# AutoReverseAVR.net
KiCad netlist of a schematic drawn in Altium Designer
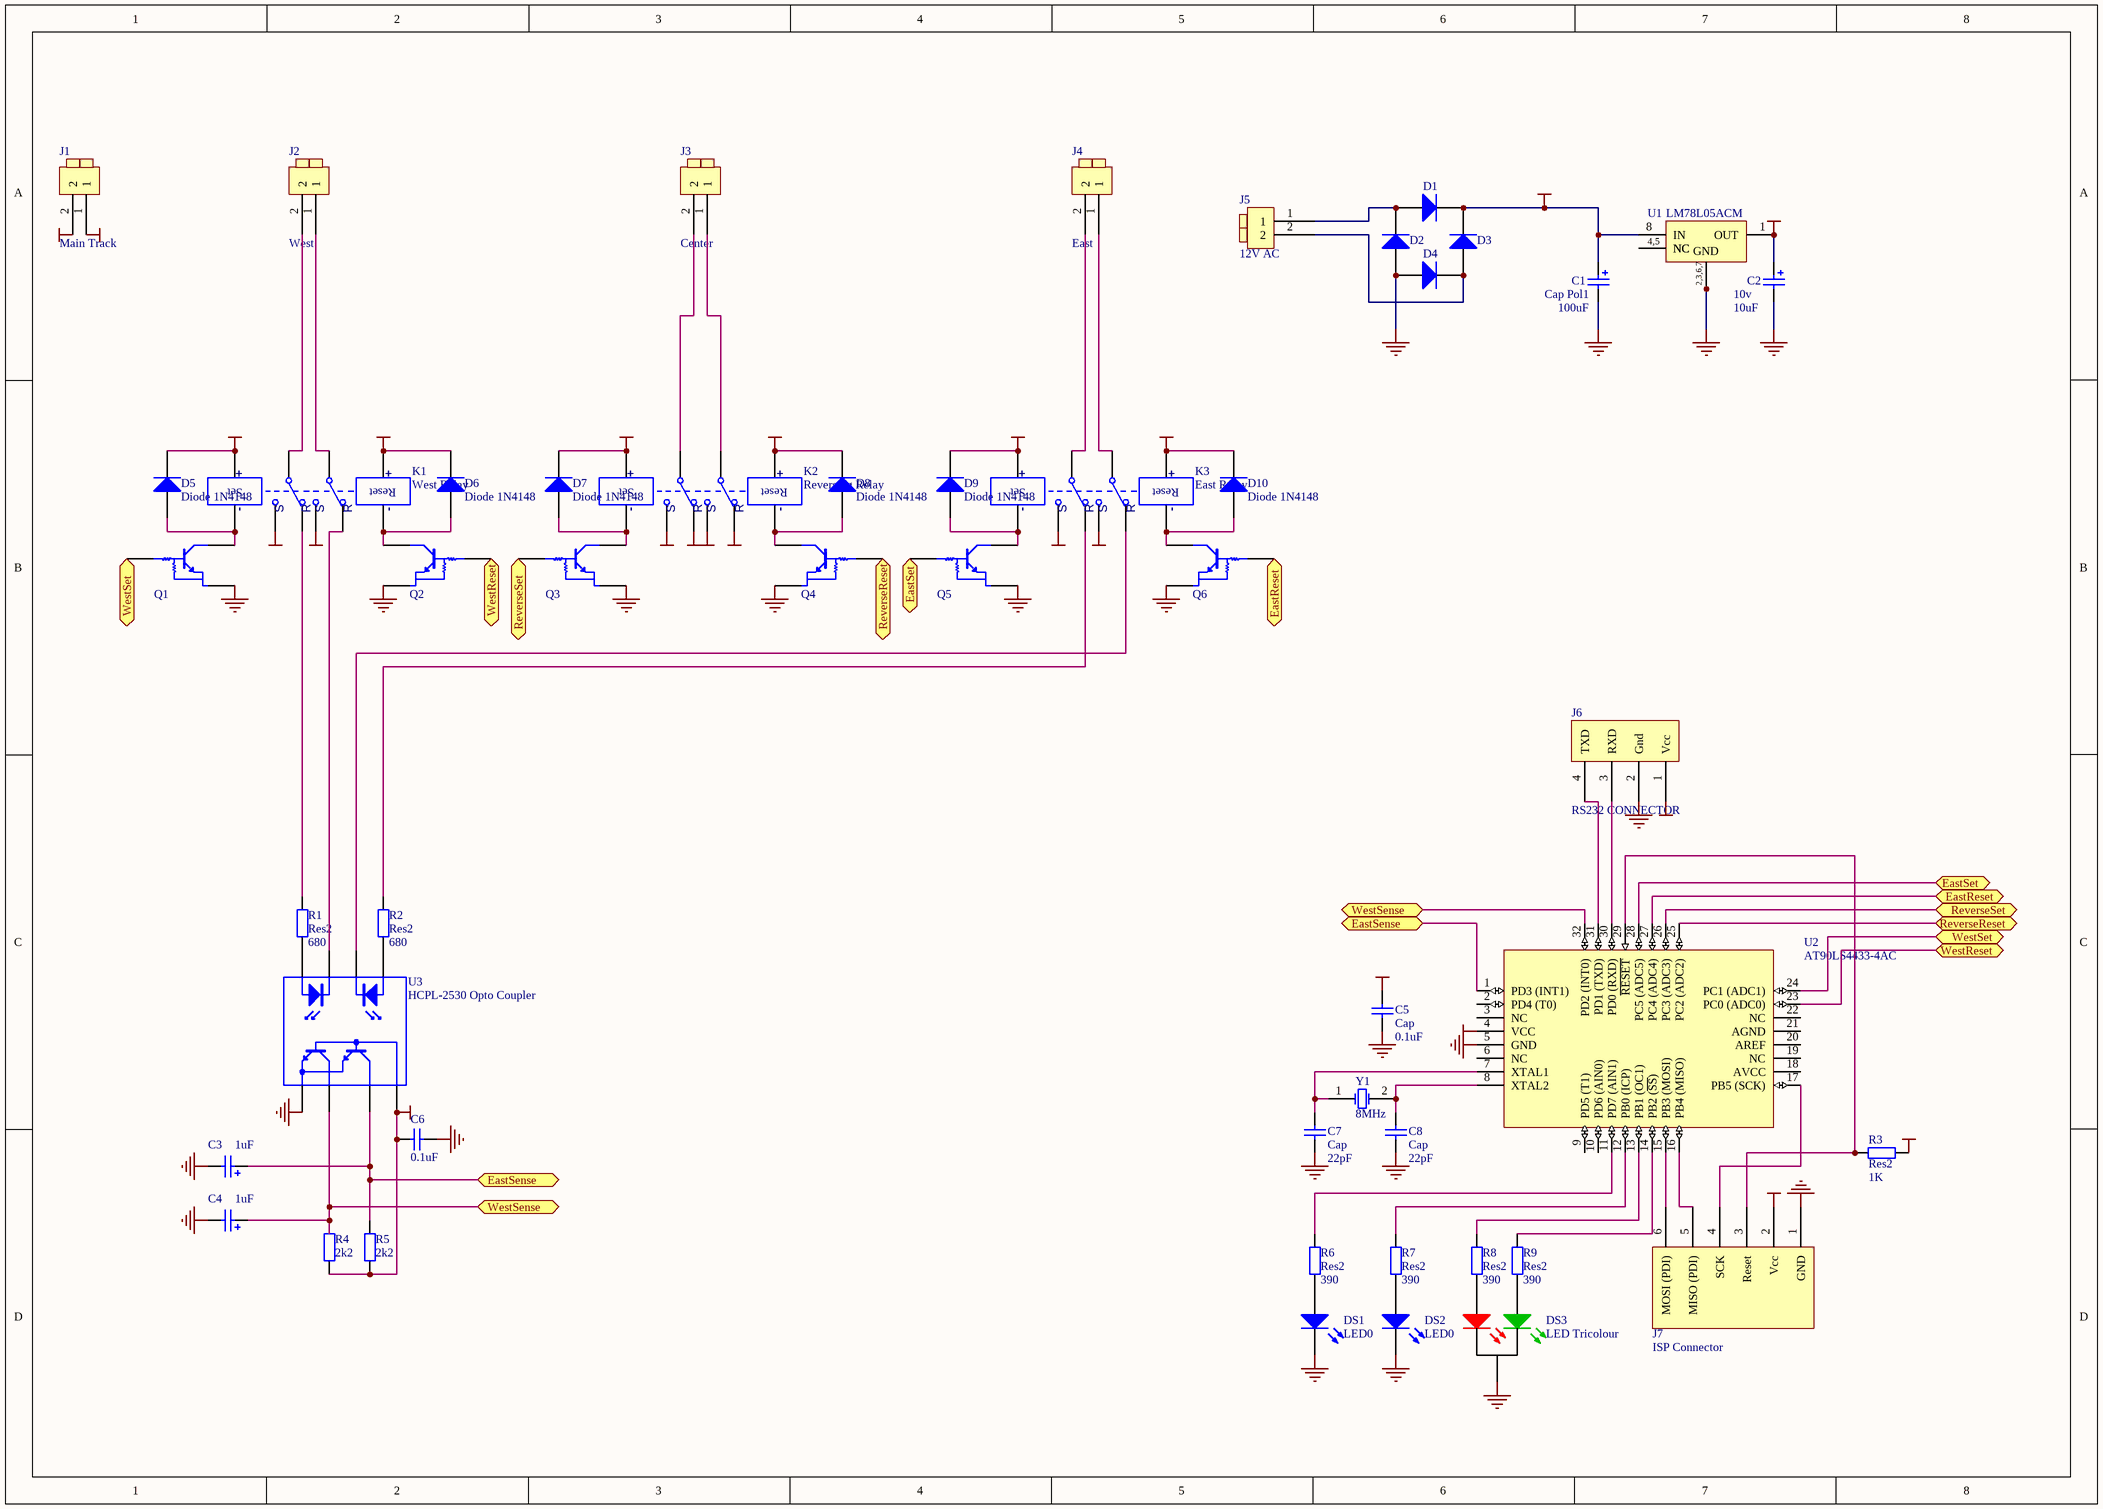
[diagram p0: AutoReverseAVR.SchDoc]

(export (version "E")
  (design (tool "Eeschema 10.0.6"))
  (components
    (comp (ref "C1")
      (value "Cap Pol1")
      (footprint "CAPPR5-10X10.5")
      (description "Polarized Capacitor (Radial)")
      (fields (field (name "ALTIUM_VALUE") "100uF") (field (name "PUBLISHER") "Altium Limited"))
      (libsource (lib "Miscellaneous Devices") (part "Cap Pol1"))
    )
    (comp (ref "C2")
      (value "10v")
      (footprint "CC3216-1206")
      (description "Polarized Capacitor (Radial)")
      (fields (field (name "ALTIUM_VALUE") "10uF") (field (name "PUBLISHER") "Altium Limited"))
      (libsource (lib "Miscellaneous Devices") (part "Cap Pol1"))
    )
    (comp (ref "C3")
      (value "1uF")
      (footprint "CC3216-1206")
      (description "Polarized Capacitor (Radial)")
      (fields (field (name "Comment") "Cap Pol1") (field (name "PUBLISHER") "Altium Limited"))
      (libsource (lib "Miscellaneous Devices") (part "Cap Pol1"))
    )
    (comp (ref "C4")
      (value "1uF")
      (footprint "CC3216-1206")
      (description "Polarized Capacitor (Radial)")
      (fields (field (name "Comment") "Cap Pol1") (field (name "PUBLISHER") "Altium Limited"))
      (libsource (lib "Miscellaneous Devices") (part "Cap Pol1"))
    )
    (comp (ref "C5")
      (value "Cap")
      (footprint "CC2012-0805")
      (description "Capacitor")
      (fields (field (name "ALTIUM_VALUE") "0.1uF") (field (name "PUBLISHER") "Altium Limited"))
      (libsource (lib "Miscellaneous Devices") (part "Cap"))
    )
    (comp (ref "C6")
      (value "0.1uF")
      (footprint "CC2012-0805")
      (description "Capacitor")
      (fields (field (name "Comment") "Cap") (field (name "PUBLISHER") "Altium Limited"))
      (libsource (lib "Miscellaneous Devices") (part "Cap"))
    )
    (comp (ref "C7")
      (value "Cap")
      (footprint "CC2012-0805")
      (description "Capacitor")
      (fields (field (name "ALTIUM_VALUE") "22pF") (field (name "PUBLISHER") "Altium Limited"))
      (libsource (lib "Miscellaneous Devices") (part "Cap"))
    )
    (comp (ref "C8")
      (value "Cap")
      (footprint "CC2012-0805")
      (description "Capacitor")
      (fields (field (name "ALTIUM_VALUE") "22pF") (field (name "PUBLISHER") "Altium Limited"))
      (libsource (lib "Miscellaneous Devices") (part "Cap"))
    )
    (comp (ref "D1")
      (value "Diode 1N4004")
      (footprint "DIO10.46-5.3x2.8")
      (description "1 Amp General Purpose Rectifier")
      (fields (field (name "PUBLISHER") "Altium Limited"))
      (libsource (lib "Miscellaneous Devices") (part "Diode 1N4004"))
    )
    (comp (ref "D2")
      (value "Diode 1N4004")
      (footprint "DIO10.46-5.3x2.8")
      (description "1 Amp General Purpose Rectifier")
      (fields (field (name "PUBLISHER") "Altium Limited"))
      (libsource (lib "Miscellaneous Devices") (part "Diode 1N4004"))
    )
    (comp (ref "D3")
      (value "Diode 1N4004")
      (footprint "DIO10.46-5.3x2.8")
      (description "1 Amp General Purpose Rectifier")
      (fields (field (name "PUBLISHER") "Altium Limited"))
      (libsource (lib "Miscellaneous Devices") (part "Diode 1N4004"))
    )
    (comp (ref "D4")
      (value "Diode 1N4004")
      (footprint "DIO10.46-5.3x2.8")
      (description "1 Amp General Purpose Rectifier")
      (fields (field (name "PUBLISHER") "Altium Limited"))
      (libsource (lib "Miscellaneous Devices") (part "Diode 1N4004"))
    )
    (comp (ref "D5")
      (value "Diode 1N4148")
      (footprint "DIO7.1-3.9x1.9")
      (description "High Conductance Fast Diode")
      (fields (field (name "PUBLISHER") "Altium Limited"))
      (libsource (lib "Miscellaneous Devices") (part "Diode 1N4148"))
    )
    (comp (ref "D6")
      (value "Diode 1N4148")
      (footprint "DIO7.1-3.9x1.9")
      (description "High Conductance Fast Diode")
      (fields (field (name "PUBLISHER") "Altium Limited"))
      (libsource (lib "Miscellaneous Devices") (part "Diode 1N4148"))
    )
    (comp (ref "D7")
      (value "Diode 1N4148")
      (footprint "DIO7.1-3.9x1.9")
      (description "High Conductance Fast Diode")
      (fields (field (name "PUBLISHER") "Altium Limited"))
      (libsource (lib "Miscellaneous Devices") (part "Diode 1N4148"))
    )
    (comp (ref "D8")
      (value "Diode 1N4148")
      (footprint "DIO7.1-3.9x1.9")
      (description "High Conductance Fast Diode")
      (fields (field (name "PUBLISHER") "Altium Limited"))
      (libsource (lib "Miscellaneous Devices") (part "Diode 1N4148"))
    )
    (comp (ref "D9")
      (value "Diode 1N4148")
      (footprint "DIO7.1-3.9x1.9")
      (description "High Conductance Fast Diode")
      (fields (field (name "PUBLISHER") "Altium Limited"))
      (libsource (lib "Miscellaneous Devices") (part "Diode 1N4148"))
    )
    (comp (ref "D10")
      (value "Diode 1N4148")
      (footprint "DIO7.1-3.9x1.9")
      (description "High Conductance Fast Diode")
      (fields (field (name "PUBLISHER") "Altium Limited"))
      (libsource (lib "Miscellaneous Devices") (part "Diode 1N4148"))
    )
    (comp (ref "DS1")
      (value "LED0")
      (footprint "LED3mm")
      (description "Typical INFRARED GaAs LED")
      (fields (field (name "PUBLISHER") "Altium Limited"))
      (libsource (lib "Miscellaneous Devices") (part "LED0"))
    )
    (comp (ref "DS2")
      (value "LED0")
      (footprint "LED3mm")
      (description "Typical INFRARED GaAs LED")
      (fields (field (name "PUBLISHER") "Altium Limited"))
      (libsource (lib "Miscellaneous Devices") (part "LED0"))
    )
    (comp (ref "DS3")
      (value "LED Tricolour")
      (footprint "LED3mm TriColour")
      (description "Typical Red Green Tri Color LED")
      (fields (field (name "PUBLISHER") "Altium Limited"))
      (libsource (lib "Custom") (part "LED Tricolour"))
    )
    (comp (ref "J1")
      (value "Main Track")
      (footprint "Screw Terminal 2 way 0.2")
      (libsource (lib "") (part "Screw Terminal 2 Way_1"))
    )
    (comp (ref "J2")
      (value "West")
      (footprint "Screw Terminal 2 way 0.2")
      (libsource (lib "") (part "Screw Terminal 2 Way_1"))
    )
    (comp (ref "J3")
      (value "Center")
      (footprint "Screw Terminal 2 way 0.2")
      (libsource (lib "") (part "Screw Terminal 2 Way_1"))
    )
    (comp (ref "J4")
      (value "East")
      (footprint "Screw Terminal 2 way 0.2")
      (libsource (lib "") (part "Screw Terminal 2 Way_1"))
    )
    (comp (ref "J5")
      (value "12V AC")
      (footprint "Screw Terminal 2 way 0.2")
      (libsource (lib "Custom") (part "Screw Terminal 2 Way"))
    )
    (comp (ref "J6")
      (value "RS232 CONNECTOR")
      (footprint "0.1 SIP 4 PIN")
      (libsource (lib "Custom") (part "RS232 CONNECTOR"))
    )
    (comp (ref "J7")
      (value "ISP Connector")
      (footprint "0.1 SIP 6 PIN")
      (libsource (lib "Custom") (part "ISP Connector"))
    )
    (comp (ref "K1")
      (value "West Relay")
      (footprint "DIP-10")
      (description "EA2-5T Dual Coil 5V Latching Relay")
      (fields (field (name "PUBLISHER") "Altium Limited"))
      (libsource (lib "Custom") (part "EA2-5T Dual Coil 5V Latching Relay"))
    )
    (comp (ref "K2")
      (value "Reversing Relay")
      (footprint "DIP-10")
      (description "EA2-5T Dual Coil 5V Latching Relay")
      (fields (field (name "PUBLISHER") "Altium Limited"))
      (libsource (lib "Custom") (part "EA2-5T Dual Coil 5V Latching Relay"))
    )
    (comp (ref "K3")
      (value "East Relay")
      (footprint "DIP-10")
      (description "EA2-5T Dual Coil 5V Latching Relay")
      (fields (field (name "PUBLISHER") "Altium Limited"))
      (libsource (lib "Custom") (part "EA2-5T Dual Coil 5V Latching Relay"))
    )
    (comp (ref "Q1")
      (value "~")
      (footprint "SO-G3")
      (description "Bias Resistor Transistor")
      (libsource (lib "Custom") (part "UN2212"))
    )
    (comp (ref "Q2")
      (value "~")
      (footprint "SO-G3")
      (description "Bias Resistor Transistor")
      (libsource (lib "Custom") (part "UN2212"))
    )
    (comp (ref "Q3")
      (value "~")
      (footprint "SO-G3")
      (description "Bias Resistor Transistor")
      (libsource (lib "Custom") (part "UN2212"))
    )
    (comp (ref "Q4")
      (value "~")
      (footprint "SO-G3")
      (description "Bias Resistor Transistor")
      (libsource (lib "Custom") (part "UN2212"))
    )
    (comp (ref "Q5")
      (value "~")
      (footprint "SO-G3")
      (description "Bias Resistor Transistor")
      (libsource (lib "Custom") (part "UN2212"))
    )
    (comp (ref "Q6")
      (value "~")
      (footprint "SO-G3")
      (description "Bias Resistor Transistor")
      (libsource (lib "Custom") (part "UN2212"))
    )
    (comp (ref "R1")
      (value "Res2")
      (footprint "CR2012-0805")
      (description "Resistor")
      (fields (field (name "ALTIUM_VALUE") "680") (field (name "PUBLISHER") "Altium Limited"))
      (libsource (lib "Miscellaneous Devices") (part "Res2"))
    )
    (comp (ref "R2")
      (value "Res2")
      (footprint "CR2012-0805")
      (description "Resistor")
      (fields (field (name "ALTIUM_VALUE") "680") (field (name "PUBLISHER") "Altium Limited"))
      (libsource (lib "Miscellaneous Devices") (part "Res2"))
    )
    (comp (ref "R3")
      (value "Res2")
      (footprint "CR2012-0805")
      (description "Resistor")
      (fields (field (name "ALTIUM_VALUE") "1K") (field (name "PUBLISHER") "Altium Limited"))
      (libsource (lib "") (part "Res2_1"))
    )
    (comp (ref "R4")
      (value "2k2")
      (footprint "CR2012-0805")
      (description "Resistor")
      (fields (field (name "Comment") "Res2") (field (name "PUBLISHER") "Altium Limited"))
      (libsource (lib "") (part "Res2_2"))
    )
    (comp (ref "R5")
      (value "2k2")
      (footprint "CR2012-0805")
      (description "Resistor")
      (fields (field (name "Comment") "Res2") (field (name "PUBLISHER") "Altium Limited"))
      (libsource (lib "") (part "Res2_2"))
    )
    (comp (ref "R6")
      (value "Res2")
      (footprint "CR2012-0805")
      (description "Resistor")
      (fields (field (name "ALTIUM_VALUE") "390") (field (name "PUBLISHER") "Altium Limited"))
      (libsource (lib "Miscellaneous Devices") (part "Res2"))
    )
    (comp (ref "R7")
      (value "Res2")
      (footprint "CR2012-0805")
      (description "Resistor")
      (fields (field (name "ALTIUM_VALUE") "390") (field (name "PUBLISHER") "Altium Limited"))
      (libsource (lib "Miscellaneous Devices") (part "Res2"))
    )
    (comp (ref "R8")
      (value "Res2")
      (footprint "CR2012-0805")
      (description "Resistor")
      (fields (field (name "ALTIUM_VALUE") "390") (field (name "PUBLISHER") "Altium Limited"))
      (libsource (lib "Miscellaneous Devices") (part "Res2"))
    )
    (comp (ref "R9")
      (value "Res2")
      (footprint "CR2012-0805")
      (description "Resistor")
      (fields (field (name "ALTIUM_VALUE") "390") (field (name "PUBLISHER") "Altium Limited"))
      (libsource (lib "Miscellaneous Devices") (part "Res2"))
    )
    (comp (ref "U1")
      (value "LM78L05ACM")
      (footprint "M08A")
      (description "3-Terminal Positive Regulator")
      (fields (field (name "PUBLISHER") "Altium Limited"))
      (libsource (lib "NSC Power Mgt Voltage Regulator") (part "LM78L05ACM"))
    )
    (comp (ref "U2")
      (value "AT90LS4433-4AC")
      (footprint "32A")
      (description "8-Bit AVR Microcontroller with 4K Bytes of In-System Programmable Flash Memory")
      (fields (field (name "PUBLISHER") "Altium Limited"))
      (libsource (lib "Custom") (part "AT90LS4433-4AC"))
    )
    (comp (ref "U3")
      (value "HCPL-2530 Opto Coupler")
      (footprint "8P3")
      (libsource (lib "Custom") (part "HCPL-2530"))
    )
    (comp (ref "Y1")
      (value "8MHz")
      (footprint "RAD-0.2")
      (description "Crystal Oscillator")
      (fields (field (name "PUBLISHER") "Altium Limited"))
      (libsource (lib "Miscellaneous Devices") (part "XTAL"))
    )
  )
  (nets
    (net (code "1") (name "/EastReset") (class "Default")
      (node (ref "Q6") (pin "1") (pinfunction "B_1") (pintype "passive"))
      (node (ref "U2") (pin "27") (pinfunction "PC4_(ADC4)_27") (pintype "bidirectional"))
    )
    (net (code "2") (name "/EastSense") (class "Default")
      (node (ref "C3") (pin "1") (pinfunction "1_1") (pintype "passive"))
      (node (ref "R5") (pin "1") (pinfunction "1_1") (pintype "passive"))
      (node (ref "U2") (pin "1") (pinfunction "PD3_(INT1)_1") (pintype "bidirectional"))
      (node (ref "U3") (pin "7") (pinfunction "C_7") (pintype "passive"))
    )
    (net (code "3") (name "/EastSet") (class "Default")
      (node (ref "Q5") (pin "1") (pinfunction "B_1") (pintype "passive"))
      (node (ref "U2") (pin "28") (pinfunction "PC5_(ADC5)_28") (pintype "bidirectional"))
    )
    (net (code "4") (name "/ReverseReset") (class "Default")
      (node (ref "Q4") (pin "1") (pinfunction "B_1") (pintype "passive"))
      (node (ref "U2") (pin "25") (pinfunction "PC2_(ADC2)_25") (pintype "bidirectional"))
    )
    (net (code "5") (name "/ReverseSet") (class "Default")
      (node (ref "Q3") (pin "1") (pinfunction "B_1") (pintype "passive"))
      (node (ref "U2") (pin "26") (pinfunction "PC3_(ADC3)_26") (pintype "bidirectional"))
    )
    (net (code "6") (name "/WestReset") (class "Default")
      (node (ref "Q2") (pin "1") (pinfunction "B_1") (pintype "passive"))
      (node (ref "U2") (pin "23") (pinfunction "PC0_(ADC0)_23") (pintype "bidirectional"))
    )
    (net (code "7") (name "/WestSense") (class "Default")
      (node (ref "C4") (pin "1") (pinfunction "1_1") (pintype "passive"))
      (node (ref "R4") (pin "1") (pinfunction "1_1") (pintype "passive"))
      (node (ref "U2") (pin "32") (pinfunction "PD2_(INT0)_32") (pintype "bidirectional"))
      (node (ref "U3") (pin "6") (pinfunction "C_6") (pintype "passive"))
    )
    (net (code "8") (name "/WestSet") (class "Default")
      (node (ref "Q1") (pin "1") (pinfunction "B_1") (pintype "passive"))
      (node (ref "U2") (pin "24") (pinfunction "PC1_(ADC1)_24") (pintype "bidirectional"))
    )
    (net (code "9") (name "A") (class "Default")
      (node (ref "J1") (pin "2") (pinfunction "2_2") (pintype "passive"))
      (node (ref "K1") (pin "7") (pinfunction "S_7") (pintype "passive"))
      (node (ref "K2") (pin "2") (pinfunction "R_2") (pintype "passive"))
      (node (ref "K2") (pin "7") (pinfunction "S_7") (pintype "passive"))
      (node (ref "K3") (pin "7") (pinfunction "S_7") (pintype "passive"))
    )
    (net (code "10") (name "B") (class "Default")
      (node (ref "J1") (pin "1") (pinfunction "1_1") (pintype "passive"))
      (node (ref "K1") (pin "4") (pinfunction "S_4") (pintype "passive"))
      (node (ref "K2") (pin "4") (pinfunction "S_4") (pintype "passive"))
      (node (ref "K2") (pin "9") (pinfunction "R_9") (pintype "passive"))
      (node (ref "K3") (pin "4") (pinfunction "S_4") (pintype "passive"))
    )
    (net (code "11") (name "GND") (class "Default")
      (node (ref "C1") (pin "2") (pinfunction "2_2") (pintype "passive"))
      (node (ref "C2") (pin "2") (pinfunction "2_2") (pintype "passive"))
      (node (ref "C3") (pin "2") (pinfunction "2_2") (pintype "passive"))
      (node (ref "C4") (pin "2") (pinfunction "2_2") (pintype "passive"))
      (node (ref "C5") (pin "1") (pinfunction "1_1") (pintype "passive"))
      (node (ref "C6") (pin "2") (pinfunction "2_2") (pintype "passive"))
      (node (ref "C7") (pin "1") (pinfunction "1_1") (pintype "passive"))
      (node (ref "C8") (pin "1") (pinfunction "1_1") (pintype "passive"))
      (node (ref "D2") (pin "1") (pinfunction "A_1") (pintype "passive"))
      (node (ref "D4") (pin "1") (pinfunction "A_1") (pintype "passive"))
      (node (ref "DS1") (pin "2") (pinfunction "K_2") (pintype "passive"))
      (node (ref "DS2") (pin "2") (pinfunction "K_2") (pintype "passive"))
      (node (ref "DS3") (pin "2") (pinfunction "K_2") (pintype "passive"))
      (node (ref "J6") (pin "2") (pinfunction "Gnd_2") (pintype "passive"))
      (node (ref "J7") (pin "1") (pinfunction "GND_1") (pintype "passive"))
      (node (ref "Q1") (pin "2") (pinfunction "E_2") (pintype "passive"))
      (node (ref "Q2") (pin "2") (pinfunction "E_2") (pintype "passive"))
      (node (ref "Q3") (pin "2") (pinfunction "E_2") (pintype "passive"))
      (node (ref "Q4") (pin "2") (pinfunction "E_2") (pintype "passive"))
      (node (ref "Q5") (pin "2") (pinfunction "E_2") (pintype "passive"))
      (node (ref "Q6") (pin "2") (pinfunction "E_2") (pintype "passive"))
      (node (ref "U1") (pin "2") (pinfunction "GND_2") (pintype "power_in"))
      (node (ref "U1") (pin "3") (pinfunction "GND_3") (pintype "power_in"))
      (node (ref "U1") (pin "6") (pinfunction "GND_6") (pintype "power_in"))
      (node (ref "U1") (pin "7") (pinfunction "GND_7") (pintype "power_in"))
      (node (ref "U2") (pin "5") (pinfunction "GND_5") (pintype "power_in"))
      (node (ref "U3") (pin "5") (pinfunction "E_5") (pintype "passive"))
    )
    (net (code "12") (name "Net-(D1-A)") (class "Default")
      (node (ref "D1") (pin "1") (pinfunction "A_1") (pintype "passive"))
      (node (ref "D2") (pin "2") (pinfunction "K_2") (pintype "passive"))
      (node (ref "J5") (pin "1") (pinfunction "1_1") (pintype "passive"))
    )
    (net (code "13") (name "Net-(D3-A)") (class "Default")
      (node (ref "D3") (pin "1") (pinfunction "A_1") (pintype "passive"))
      (node (ref "D4") (pin "2") (pinfunction "K_2") (pintype "passive"))
      (node (ref "J5") (pin "2") (pinfunction "2_2") (pintype "passive"))
    )
    (net (code "14") (name "Net-(D5-A)") (class "Default")
      (node (ref "D5") (pin "1") (pinfunction "A_1") (pintype "passive"))
      (node (ref "K1") (pin "5") (pintype "passive"))
      (node (ref "Q1") (pin "3") (pinfunction "C_3") (pintype "passive"))
    )
    (net (code "15") (name "Net-(D6-A)") (class "Default")
      (node (ref "D6") (pin "1") (pinfunction "A_1") (pintype "passive"))
      (node (ref "K1") (pin "6") (pintype "passive"))
      (node (ref "Q2") (pin "3") (pinfunction "C_3") (pintype "passive"))
    )
    (net (code "16") (name "Net-(D7-A)") (class "Default")
      (node (ref "D7") (pin "1") (pinfunction "A_1") (pintype "passive"))
      (node (ref "K2") (pin "5") (pintype "passive"))
      (node (ref "Q3") (pin "3") (pinfunction "C_3") (pintype "passive"))
    )
    (net (code "17") (name "Net-(D8-A)") (class "Default")
      (node (ref "D8") (pin "1") (pinfunction "A_1") (pintype "passive"))
      (node (ref "K2") (pin "6") (pintype "passive"))
      (node (ref "Q4") (pin "3") (pinfunction "C_3") (pintype "passive"))
    )
    (net (code "18") (name "Net-(D9-A)") (class "Default")
      (node (ref "D9") (pin "1") (pinfunction "A_1") (pintype "passive"))
      (node (ref "K3") (pin "5") (pintype "passive"))
      (node (ref "Q5") (pin "3") (pinfunction "C_3") (pintype "passive"))
    )
    (net (code "19") (name "Net-(D10-A)") (class "Default")
      (node (ref "D10") (pin "1") (pinfunction "A_1") (pintype "passive"))
      (node (ref "K3") (pin "6") (pintype "passive"))
      (node (ref "Q6") (pin "3") (pinfunction "C_3") (pintype "passive"))
    )
    (net (code "20") (name "Net-(DS1-A)") (class "Default")
      (node (ref "DS1") (pin "1") (pinfunction "A_1") (pintype "passive"))
      (node (ref "R6") (pin "1") (pinfunction "1_1") (pintype "passive"))
    )
    (net (code "21") (name "Net-(DS2-A)") (class "Default")
      (node (ref "DS2") (pin "1") (pinfunction "A_1") (pintype "passive"))
      (node (ref "R7") (pin "1") (pinfunction "1_1") (pintype "passive"))
    )
    (net (code "22") (name "Net-(DS3-Ag)") (class "Default")
      (node (ref "DS3") (pin "1") (pinfunction "Ag_1") (pintype "passive"))
      (node (ref "R9") (pin "1") (pinfunction "1_1") (pintype "passive"))
    )
    (net (code "23") (name "Net-(DS3-Ar)") (class "Default")
      (node (ref "DS3") (pin "3") (pinfunction "Ar_3") (pintype "passive"))
      (node (ref "R8") (pin "1") (pinfunction "1_1") (pintype "passive"))
    )
    (net (code "24") (name "Net-(J2-Pad1)") (class "Default")
      (node (ref "J2") (pin "1") (pinfunction "1_1") (pintype "passive"))
      (node (ref "K1") (pin "3") (pinfunction "3_3") (pintype "passive"))
    )
    (net (code "25") (name "Net-(J2-Pad2)") (class "Default")
      (node (ref "J2") (pin "2") (pinfunction "2_2") (pintype "passive"))
      (node (ref "K1") (pin "8") (pinfunction "8_8") (pintype "passive"))
    )
    (net (code "26") (name "Net-(J3-Pad1)") (class "Default")
      (node (ref "J3") (pin "1") (pinfunction "1_1") (pintype "passive"))
      (node (ref "K2") (pin "3") (pinfunction "3_3") (pintype "passive"))
    )
    (net (code "27") (name "Net-(J3-Pad2)") (class "Default")
      (node (ref "J3") (pin "2") (pinfunction "2_2") (pintype "passive"))
      (node (ref "K2") (pin "8") (pinfunction "8_8") (pintype "passive"))
    )
    (net (code "28") (name "Net-(J4-Pad1)") (class "Default")
      (node (ref "J4") (pin "1") (pinfunction "1_1") (pintype "passive"))
      (node (ref "K3") (pin "3") (pinfunction "3_3") (pintype "passive"))
    )
    (net (code "29") (name "Net-(J4-Pad2)") (class "Default")
      (node (ref "J4") (pin "2") (pinfunction "2_2") (pintype "passive"))
      (node (ref "K3") (pin "8") (pinfunction "8_8") (pintype "passive"))
    )
    (net (code "30") (name "Net-(J6-RXD)") (class "Default")
      (node (ref "J6") (pin "3") (pinfunction "RXD_3") (pintype "passive"))
      (node (ref "U2") (pin "30") (pinfunction "PD0_(RXD)_30") (pintype "bidirectional"))
    )
    (net (code "31") (name "Net-(J6-TXD)") (class "Default")
      (node (ref "J6") (pin "4") (pinfunction "TXD_4") (pintype "passive"))
      (node (ref "U2") (pin "31") (pinfunction "PD1_(TXD)_31") (pintype "bidirectional"))
    )
    (net (code "32") (name "Net-(J7-MISO_(PDI))") (class "Default")
      (node (ref "J7") (pin "5") (pinfunction "MISO_(PDI)_5") (pintype "passive"))
      (node (ref "U2") (pin "16") (pinfunction "PB4_(MISO)_16") (pintype "bidirectional"))
    )
    (net (code "33") (name "Net-(J7-MOSI_(PDI))") (class "Default")
      (node (ref "J7") (pin "6") (pinfunction "MOSI_(PDI)_6") (pintype "passive"))
      (node (ref "U2") (pin "15") (pinfunction "PB3_(MOSI)_15") (pintype "bidirectional"))
    )
    (net (code "34") (name "Net-(J7-Reset)") (class "Default")
      (node (ref "J7") (pin "3") (pinfunction "Reset_3") (pintype "passive"))
      (node (ref "R3") (pin "2") (pinfunction "2_2") (pintype "passive"))
      (node (ref "U2") (pin "29") (pinfunction "~{RESET}_29") (pintype "input"))
    )
    (net (code "35") (name "Net-(J7-SCK)") (class "Default")
      (node (ref "J7") (pin "4") (pinfunction "SCK_4") (pintype "passive"))
      (node (ref "U2") (pin "17") (pinfunction "PB5_(SCK)_17") (pintype "bidirectional"))
    )
    (net (code "36") (name "Net-(K1-R-Pad2)") (class "Default")
      (node (ref "K1") (pin "2") (pinfunction "R_2") (pintype "passive"))
      (node (ref "U3") (pin "3") (pinfunction "K_3") (pintype "passive"))
    )
    (net (code "37") (name "Net-(K1-R-Pad9)") (class "Default")
      (node (ref "K1") (pin "9") (pinfunction "R_9") (pintype "passive"))
      (node (ref "R1") (pin "2") (pinfunction "2_2") (pintype "passive"))
    )
    (net (code "38") (name "Net-(K3-R-Pad2)") (class "Default")
      (node (ref "K3") (pin "2") (pinfunction "R_2") (pintype "passive"))
      (node (ref "U3") (pin "2") (pinfunction "K_2") (pintype "passive"))
    )
    (net (code "39") (name "Net-(K3-R-Pad9)") (class "Default")
      (node (ref "K3") (pin "9") (pinfunction "R_9") (pintype "passive"))
      (node (ref "R2") (pin "2") (pinfunction "2_2") (pintype "passive"))
    )
    (net (code "40") (name "Net-(R1-Pad1)") (class "Default")
      (node (ref "R1") (pin "1") (pinfunction "1_1") (pintype "passive"))
      (node (ref "U3") (pin "4") (pinfunction "A_4") (pintype "passive"))
    )
    (net (code "41") (name "Net-(R2-Pad1)") (class "Default")
      (node (ref "R2") (pin "1") (pinfunction "1_1") (pintype "passive"))
      (node (ref "U3") (pin "1") (pinfunction "A_1") (pintype "passive"))
    )
    (net (code "42") (name "Net-(U1-NC-Pad4)") (class "Default")
      (node (ref "U1") (pin "4") (pinfunction "NC_4") (pintype "passive"))
      (node (ref "U1") (pin "5") (pinfunction "NC_5") (pintype "passive"))
    )
    (net (code "43") (name "Net-(U2-PB0_(ICP))") (class "Default")
      (node (ref "R7") (pin "2") (pinfunction "2_2") (pintype "passive"))
      (node (ref "U2") (pin "12") (pinfunction "PB0_(ICP)_12") (pintype "bidirectional"))
    )
    (net (code "44") (name "Net-(U2-PB1_(OC1))") (class "Default")
      (node (ref "R8") (pin "2") (pinfunction "2_2") (pintype "passive"))
      (node (ref "U2") (pin "13") (pinfunction "PB1_(OC1)_13") (pintype "bidirectional"))
    )
    (net (code "45") (name "Net-(U2-PB2_(~{SS}))") (class "Default")
      (node (ref "R9") (pin "2") (pinfunction "2_2") (pintype "passive"))
      (node (ref "U2") (pin "14") (pinfunction "PB2_(~{SS})_14") (pintype "bidirectional"))
    )
    (net (code "46") (name "Net-(U2-PD7_(AIN1))") (class "Default")
      (node (ref "R6") (pin "2") (pinfunction "2_2") (pintype "passive"))
      (node (ref "U2") (pin "11") (pinfunction "PD7_(AIN1)_11") (pintype "bidirectional"))
    )
    (net (code "47") (name "Net-(U2-XTAL1)") (class "Default")
      (node (ref "C7") (pin "2") (pinfunction "2_2") (pintype "passive"))
      (node (ref "U2") (pin "7") (pinfunction "XTAL1_7") (pintype "passive"))
      (node (ref "Y1") (pin "1") (pinfunction "OSC1_1") (pintype "passive"))
    )
    (net (code "48") (name "Net-(U2-XTAL2)") (class "Default")
      (node (ref "C8") (pin "2") (pinfunction "2_2") (pintype "passive"))
      (node (ref "U2") (pin "8") (pinfunction "XTAL2_8") (pintype "passive"))
      (node (ref "Y1") (pin "2") (pinfunction "OSC2_2") (pintype "passive"))
    )
    (net (code "49") (name "VCC") (class "Default")
      (node (ref "C2") (pin "1") (pinfunction "1_1") (pintype "passive"))
      (node (ref "C5") (pin "2") (pinfunction "2_2") (pintype "passive"))
      (node (ref "C6") (pin "1") (pinfunction "1_1") (pintype "passive"))
      (node (ref "J6") (pin "1") (pinfunction "Vcc_1") (pintype "passive"))
      (node (ref "J7") (pin "2") (pinfunction "Vcc_2") (pintype "passive"))
      (node (ref "R3") (pin "1") (pinfunction "1_1") (pintype "passive"))
      (node (ref "R4") (pin "2") (pinfunction "2_2") (pintype "passive"))
      (node (ref "R5") (pin "2") (pinfunction "2_2") (pintype "passive"))
      (node (ref "U1") (pin "1") (pinfunction "OUT_1") (pintype "power_in"))
      (node (ref "U2") (pin "4") (pinfunction "VCC_4") (pintype "power_in"))
      (node (ref "U3") (pin "8") (pinfunction "E_8") (pintype "passive"))
    )
    (net (code "50") (name "Vdd") (class "Default")
      (node (ref "C1") (pin "1") (pinfunction "1_1") (pintype "passive"))
      (node (ref "D1") (pin "2") (pinfunction "K_2") (pintype "passive"))
      (node (ref "D10") (pin "2") (pinfunction "K_2") (pintype "passive"))
      (node (ref "D3") (pin "2") (pinfunction "K_2") (pintype "passive"))
      (node (ref "D5") (pin "2") (pinfunction "K_2") (pintype "passive"))
      (node (ref "D6") (pin "2") (pinfunction "K_2") (pintype "passive"))
      (node (ref "D7") (pin "2") (pinfunction "K_2") (pintype "passive"))
      (node (ref "D8") (pin "2") (pinfunction "K_2") (pintype "passive"))
      (node (ref "D9") (pin "2") (pinfunction "K_2") (pintype "passive"))
      (node (ref "K1") (pin "1") (pintype "passive"))
      (node (ref "K1") (pin "10") (pintype "passive"))
      (node (ref "K2") (pin "1") (pintype "passive"))
      (node (ref "K2") (pin "10") (pintype "passive"))
      (node (ref "K3") (pin "1") (pintype "passive"))
      (node (ref "K3") (pin "10") (pintype "passive"))
      (node (ref "U1") (pin "8") (pinfunction "IN_8") (pintype "power_in"))
    )
    (net (code "51") (name "unconnected-(U2-AGND-Pad21)") (class "Default")
      (node (ref "U2") (pin "21") (pinfunction "AGND_21") (pintype "power_in"))
    )
    (net (code "52") (name "unconnected-(U2-AREF-Pad20)") (class "Default")
      (node (ref "U2") (pin "20") (pinfunction "AREF_20") (pintype "passive"))
    )
    (net (code "53") (name "unconnected-(U2-AVCC-Pad18)") (class "Default")
      (node (ref "U2") (pin "18") (pinfunction "AVCC_18") (pintype "power_in"))
    )
    (net (code "54") (name "unconnected-(U2-NC-Pad3)") (class "Default")
      (node (ref "U2") (pin "3") (pinfunction "NC_3") (pintype "passive"))
    )
    (net (code "55") (name "unconnected-(U2-NC-Pad6)") (class "Default")
      (node (ref "U2") (pin "6") (pinfunction "NC_6") (pintype "passive"))
    )
    (net (code "56") (name "unconnected-(U2-NC-Pad19)") (class "Default")
      (node (ref "U2") (pin "19") (pinfunction "NC_19") (pintype "passive"))
    )
    (net (code "57") (name "unconnected-(U2-NC-Pad22)") (class "Default")
      (node (ref "U2") (pin "22") (pinfunction "NC_22") (pintype "passive"))
    )
    (net (code "58") (name "unconnected-(U2-PD4_(T0)-Pad2)") (class "Default")
      (node (ref "U2") (pin "2") (pinfunction "PD4_(T0)_2") (pintype "bidirectional"))
    )
    (net (code "59") (name "unconnected-(U2-PD5_(T1)-Pad9)") (class "Default")
      (node (ref "U2") (pin "9") (pinfunction "PD5_(T1)_9") (pintype "bidirectional"))
    )
    (net (code "60") (name "unconnected-(U2-PD6_(AIN0)-Pad10)") (class "Default")
      (node (ref "U2") (pin "10") (pinfunction "PD6_(AIN0)_10") (pintype "bidirectional"))
    )
  )
)
